# Moisture_sensor.net
KiCad netlist of a schematic drawn in EAGLE
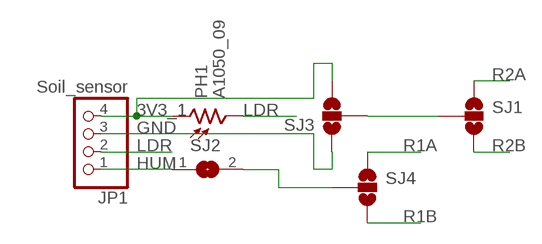
[diagram p0: schematic, sheet 1]

(export (version "E")
  (design (tool "Eeschema 10.0.6"))
  (components
    (comp (ref "JP1")
      (value "Soil_sensor")
      (footprint "eagle-import:1X04")
      (libsource (lib "eagle-import") (part "PINHD-1X4"))
    )
    (comp (ref "PH1")
      (value "A1050_09")
      (footprint "eagle-import:T0-46-A10XX")
      (libsource (lib "eagle-import") (part "A1050_09"))
    )
    (comp (ref "SJ1")
      (value "SOLDERJUMPER_2WAYS")
      (footprint "eagle-import:SJ_3")
      (libsource (lib "eagle-import") (part "SOLDERJUMPER_2WAYS"))
    )
    (comp (ref "SJ2") (value "SJ") (footprint "eagle-import:SJ") (libsource (lib "eagle-import") (part "SJ")))
    (comp (ref "SJ3")
      (value "SOLDERJUMPER_2WAYS")
      (footprint "eagle-import:SJ_3")
      (libsource (lib "eagle-import") (part "SOLDERJUMPER_2WAYS"))
    )
    (comp (ref "SJ4")
      (value "SOLDERJUMPER_2WAYS")
      (footprint "eagle-import:SJ_3")
      (libsource (lib "eagle-import") (part "SOLDERJUMPER_2WAYS"))
    )
  )
  (nets
    (net (code "1") (name "/3V3_1") (class "Default")
      (node (ref "JP1") (pin "4") (pinfunction "4_4") (pintype "passive"))
      (node (ref "PH1") (pin "1") (pinfunction "1_1") (pintype "passive"))
      (node (ref "SJ3") (pin "3") (pinfunction "3_3") (pintype "passive"))
    )
    (net (code "2") (name "/GND") (class "Default")
      (node (ref "JP1") (pin "3") (pinfunction "3_3") (pintype "passive"))
      (node (ref "SJ3") (pin "1") (pinfunction "1_1") (pintype "passive"))
    )
    (net (code "3") (name "/HUM") (class "Default")
      (node (ref "JP1") (pin "1") (pinfunction "1_1") (pintype "passive"))
      (node (ref "SJ2") (pin "1") (pinfunction "1_1") (pintype "passive"))
    )
    (net (code "4") (name "/LDR") (class "Default")
      (node (ref "JP1") (pin "2") (pinfunction "2_2") (pintype "passive"))
      (node (ref "PH1") (pin "2") (pinfunction "2_2") (pintype "passive"))
    )
    (net (code "5") (name "/R1A") (class "Default")
      (node (ref "SJ4") (pin "1") (pinfunction "1_1") (pintype "passive"))
    )
    (net (code "6") (name "/R1B") (class "Default")
      (node (ref "SJ4") (pin "3") (pinfunction "3_3") (pintype "passive"))
    )
    (net (code "7") (name "/R2A") (class "Default")
      (node (ref "SJ1") (pin "1") (pinfunction "1_1") (pintype "passive"))
    )
    (net (code "8") (name "/R2B") (class "Default")
      (node (ref "SJ1") (pin "3") (pinfunction "3_3") (pintype "passive"))
    )
    (net (code "9") (name "Net-(SJ1-Pad2)") (class "Default")
      (node (ref "SJ1") (pin "2") (pinfunction "2_2") (pintype "passive"))
      (node (ref "SJ3") (pin "2") (pinfunction "2_2") (pintype "passive"))
    )
    (net (code "10") (name "Net-(SJ2-Pad2)") (class "Default")
      (node (ref "SJ2") (pin "2") (pinfunction "2_2") (pintype "passive"))
      (node (ref "SJ4") (pin "2") (pinfunction "2_2") (pintype "passive"))
    )
  )
)
